# efm8bb1-breakout.net
KiCad netlist of a schematic drawn in Altium Designer
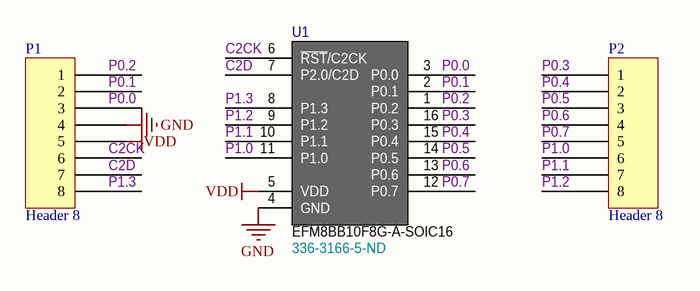
[diagram p0: efm8bb1-breakout.SchDoc]

(export (version "E")
  (design (tool "Eeschema 10.0.6"))
  (components
    (comp (ref "P1")
      (value "Header 8")
      (footprint "HDR1X8-NOSILK-PINS")
      (description "Header, 8-Pin")
      (fields (field (name "PUBLISHER") "Altium Limited"))
      (libsource (lib "") (part "Header 8_1"))
    )
    (comp (ref "P2")
      (value "Header 8")
      (footprint "HDR1X8-NOSILK-PINS")
      (description "Header, 8-Pin")
      (fields (field (name "PUBLISHER") "Altium Limited"))
      (libsource (lib "Miscellaneous Connectors") (part "Header 8"))
    )
    (comp (ref "U1")
      (value "EFM8BB10F8G-A-SOIC16")
      (footprint "SOIC127P600-16N")
      (description "IC MCU 8BIT 8KB FLASH 16SOIC")
      (fields
        (field (name "MANUFACTURER") "Silicon Labs")
        (field (name "SUPPLIER PART NUMBER 1") "336-3166-5-ND")
      )
      (libsource (lib "SiLabs 8-bit MCU") (part "EFM8BB10F8G-A-SOIC16"))
    )
  )
  (nets
    (net (code "1") (name "/C2CK") (class "Default")
      (node (ref "P1") (pin "6") (pinfunction "6_6") (pintype "passive"))
      (node (ref "U1") (pin "6") (pinfunction "~{RST}/C2CK_6") (pintype "power_in"))
    )
    (net (code "2") (name "/C2D") (class "Default")
      (node (ref "P1") (pin "7") (pinfunction "7_7") (pintype "passive"))
      (node (ref "U1") (pin "7") (pinfunction "P2.0/C2D_7") (pintype "power_in"))
    )
    (net (code "3") (name "/P0.0") (class "Default")
      (node (ref "P1") (pin "3") (pinfunction "3_3") (pintype "passive"))
      (node (ref "U1") (pin "3") (pinfunction "P0.0_3") (pintype "power_in"))
    )
    (net (code "4") (name "/P0.1") (class "Default")
      (node (ref "P1") (pin "2") (pinfunction "2_2") (pintype "passive"))
      (node (ref "U1") (pin "2") (pinfunction "P0.1_2") (pintype "power_in"))
    )
    (net (code "5") (name "/P0.2") (class "Default")
      (node (ref "P1") (pin "1") (pinfunction "1_1") (pintype "passive"))
      (node (ref "U1") (pin "1") (pinfunction "P0.2_1") (pintype "power_in"))
    )
    (net (code "6") (name "/P0.3") (class "Default")
      (node (ref "P2") (pin "1") (pinfunction "1_1") (pintype "passive"))
      (node (ref "U1") (pin "16") (pinfunction "P0.3_16") (pintype "power_in"))
    )
    (net (code "7") (name "/P0.4") (class "Default")
      (node (ref "P2") (pin "2") (pinfunction "2_2") (pintype "passive"))
      (node (ref "U1") (pin "15") (pinfunction "P0.4_15") (pintype "power_in"))
    )
    (net (code "8") (name "/P0.5") (class "Default")
      (node (ref "P2") (pin "3") (pinfunction "3_3") (pintype "passive"))
      (node (ref "U1") (pin "14") (pinfunction "P0.5_14") (pintype "power_in"))
    )
    (net (code "9") (name "/P0.6") (class "Default")
      (node (ref "P2") (pin "4") (pinfunction "4_4") (pintype "passive"))
      (node (ref "U1") (pin "13") (pinfunction "P0.6_13") (pintype "power_in"))
    )
    (net (code "10") (name "/P0.7") (class "Default")
      (node (ref "P2") (pin "5") (pinfunction "5_5") (pintype "passive"))
      (node (ref "U1") (pin "12") (pinfunction "P0.7_12") (pintype "power_in"))
    )
    (net (code "11") (name "/P1.0") (class "Default")
      (node (ref "P2") (pin "6") (pinfunction "6_6") (pintype "passive"))
      (node (ref "U1") (pin "11") (pinfunction "P1.0_11") (pintype "power_in"))
    )
    (net (code "12") (name "/P1.1") (class "Default")
      (node (ref "P2") (pin "7") (pinfunction "7_7") (pintype "passive"))
      (node (ref "U1") (pin "10") (pinfunction "P1.1_10") (pintype "power_in"))
    )
    (net (code "13") (name "/P1.2") (class "Default")
      (node (ref "P2") (pin "8") (pinfunction "8_8") (pintype "passive"))
      (node (ref "U1") (pin "9") (pinfunction "P1.2_9") (pintype "power_in"))
    )
    (net (code "14") (name "/P1.3") (class "Default")
      (node (ref "P1") (pin "8") (pinfunction "8_8") (pintype "passive"))
      (node (ref "U1") (pin "8") (pinfunction "P1.3_8") (pintype "power_in"))
    )
    (net (code "15") (name "GND") (class "Default")
      (node (ref "P1") (pin "4") (pinfunction "4_4") (pintype "passive"))
      (node (ref "U1") (pin "4") (pinfunction "GND_4") (pintype "power_in"))
    )
    (net (code "16") (name "VDD") (class "Default")
      (node (ref "P1") (pin "5") (pinfunction "5_5") (pintype "passive"))
      (node (ref "U1") (pin "5") (pinfunction "VDD_5") (pintype "power_in"))
    )
  )
)
